# MQ3.net
KiCad netlist of a schematic drawn in Altium Designer
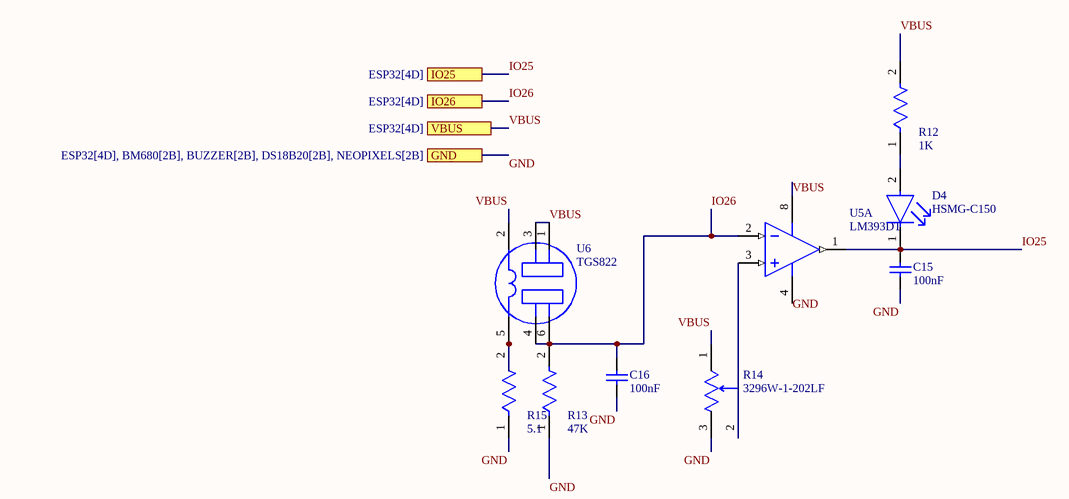
[diagram p0: MQ3.SchDoc]

(export (version "E")
  (design (tool "Eeschema 10.0.6"))
  (components
    (comp (ref "C15")
      (value "100nF")
      (footprint "CAPC2013X140X50LL20T25")
      (description "10µF ±10% 16V Ceramic Capacitor X5R 0805 (2012 Metric)")
      (fields (field (name "PART NUMBER") "CL21A106KOQNNNG"))
      (libsource (lib "Altium Content Vault") (part "CAP"))
    )
    (comp (ref "C16")
      (value "100nF")
      (footprint "CAPC2013X140X50LL20T25")
      (description "10µF ±10% 16V Ceramic Capacitor X5R 0805 (2012 Metric)")
      (fields (field (name "PART NUMBER") "CL21A106KOQNNNG"))
      (libsource (lib "Altium Content Vault") (part "CAP"))
    )
    (comp (ref "D4")
      (value "HSMG-C150")
      (footprint "FP-HSMG-C150-MFG")
      (description "LED GREEN DIFFUSED 1206 SMD")
      (fields
        (field (name "MANUFACTURER") "Broadcom")
        (field (name "OCTOPART") "https://octopart.com/hsmg-c150-broadcom-71131304")
      )
      (libsource (lib "Altium Content Vault") (part "8706943c75ba83719d021d2fdc84c58"))
    )
    (comp (ref "R12")
      (value "1K")
      (footprint "FP-ERA6A-IPC_B")
      (description "RES 100K OHM 0.1% 1/8W 0805")
      (fields (field (name "TOLERANCE") "0.1%"))
      (libsource (lib "Altium Content Vault") (part "1029c3af85768c4190bb7ad29bc67b5"))
    )
    (comp (ref "R13")
      (value "47K")
      (footprint "FP-ERA6A-IPC_A")
      (description "RES 100K OHM 0.1% 1/8W 0805")
      (fields (field (name "TOLERANCE") "0.1%"))
      (libsource (lib "Altium Content Vault") (part "1029c3af85768c4190bb7ad29bc67b5"))
    )
    (comp (ref "R14")
      (value "3296W-1-202LF")
      (footprint "FP-3296W-MFG")
      (description "TRIMMER 2K OHM 0.5W PC PIN TOP")
      (fields (field (name "TOLERANCE") "10%"))
      (libsource (lib "Altium Content Vault") (part "81a8d1f2e6c155a1fa928b358d1a42a"))
    )
    (comp (ref "R15")
      (value "5.1")
      (footprint "FP-ERA6A-IPC_A")
      (description "RES 100K OHM 0.1% 1/8W 0805")
      (fields (field (name "TOLERANCE") "0.1%"))
      (libsource (lib "Altium Content Vault") (part "1029c3af85768c4190bb7ad29bc67b5"))
    )
    (comp (ref "U5")
      (value "LM393DT")
      (footprint "STM-SO-8_D_L")
      (description "Low-Power, Dual-Voltage Comparator, 2 to 36 V, 0 to 70 degC, 8-Pin SOIC (SO), RoHS, Tape and Reel")
      (fields (field (name "MANUFACTURER") "STMicroelectronics"))
      (libsource (lib "Altium Content Vault") (part "STM-LM393-SO8"))
    )
    (comp (ref "U6")
      (value "TGS822")
      (footprint "FP-TGS822-MFG")
      (description "TGS822 MOS-Type organic solvent vapors sensor; range: 50-5000ppm C2H5OH; supply: 5V; power: 660mW")
      (libsource (lib "Altium Content Vault") (part "177b91c4a673ff2773236b1cb9aa546"))
    )
  )
  (nets
    (net (code "1") (name "/GND") (class "Default")
      (node (ref "C15") (pin "1") (pinfunction "1_1") (pintype "passive"))
      (node (ref "C16") (pin "1") (pinfunction "1_1") (pintype "passive"))
      (node (ref "R13") (pin "1") (pinfunction "1_1") (pintype "passive"))
      (node (ref "R14") (pin "3") (pinfunction "CW_3") (pintype "passive"))
      (node (ref "R15") (pin "1") (pinfunction "1_1") (pintype "passive"))
      (node (ref "U5") (pin "4") (pinfunction "VCC-_4") (pintype "power_in"))
    )
    (net (code "2") (name "/IO25") (class "Default")
      (node (ref "C15") (pin "2") (pinfunction "2_2") (pintype "passive"))
      (node (ref "D4") (pin "1") (pinfunction "C_1") (pintype "passive"))
      (node (ref "U5") (pin "1") (pinfunction "OUT1_1") (pintype "output"))
    )
    (net (code "3") (name "/IO26") (class "Default")
      (node (ref "C16") (pin "2") (pinfunction "2_2") (pintype "passive"))
      (node (ref "R13") (pin "2") (pinfunction "2_2") (pintype "passive"))
      (node (ref "U5") (pin "2") (pinfunction "IN1-_2") (pintype "input"))
      (node (ref "U6") (pin "4") (pinfunction "VRL_4") (pintype "passive"))
      (node (ref "U6") (pin "6") (pinfunction "VRL_6") (pintype "passive"))
    )
    (net (code "4") (name "/VBUS") (class "Default")
      (node (ref "R12") (pin "2") (pinfunction "2_2") (pintype "passive"))
      (node (ref "R14") (pin "1") (pinfunction "CCW_1") (pintype "passive"))
      (node (ref "U5") (pin "8") (pinfunction "VCC+_8") (pintype "power_in"))
      (node (ref "U6") (pin "1") (pinfunction "VC_1") (pintype "power_in"))
      (node (ref "U6") (pin "2") (pinfunction "VH_2") (pintype "power_in"))
      (node (ref "U6") (pin "3") (pinfunction "VC_3") (pintype "power_in"))
    )
    (net (code "5") (name "Net-(D4-A)") (class "Default")
      (node (ref "D4") (pin "2") (pinfunction "A_2") (pintype "passive"))
      (node (ref "R12") (pin "1") (pinfunction "1_1") (pintype "passive"))
    )
    (net (code "6") (name "Net-(R14-WIPER)") (class "Default")
      (node (ref "R14") (pin "2") (pinfunction "WIPER_2") (pintype "passive"))
      (node (ref "U5") (pin "3") (pinfunction "IN1+_3") (pintype "input"))
    )
    (net (code "7") (name "Net-(U6-GND)") (class "Default")
      (node (ref "R15") (pin "2") (pinfunction "2_2") (pintype "passive"))
      (node (ref "U6") (pin "5") (pinfunction "GND_5") (pintype "power_in"))
    )
  )
)
